# ble_lock_V1_2-20201223.net
KiCad netlist of a schematic drawn in Altium Designer
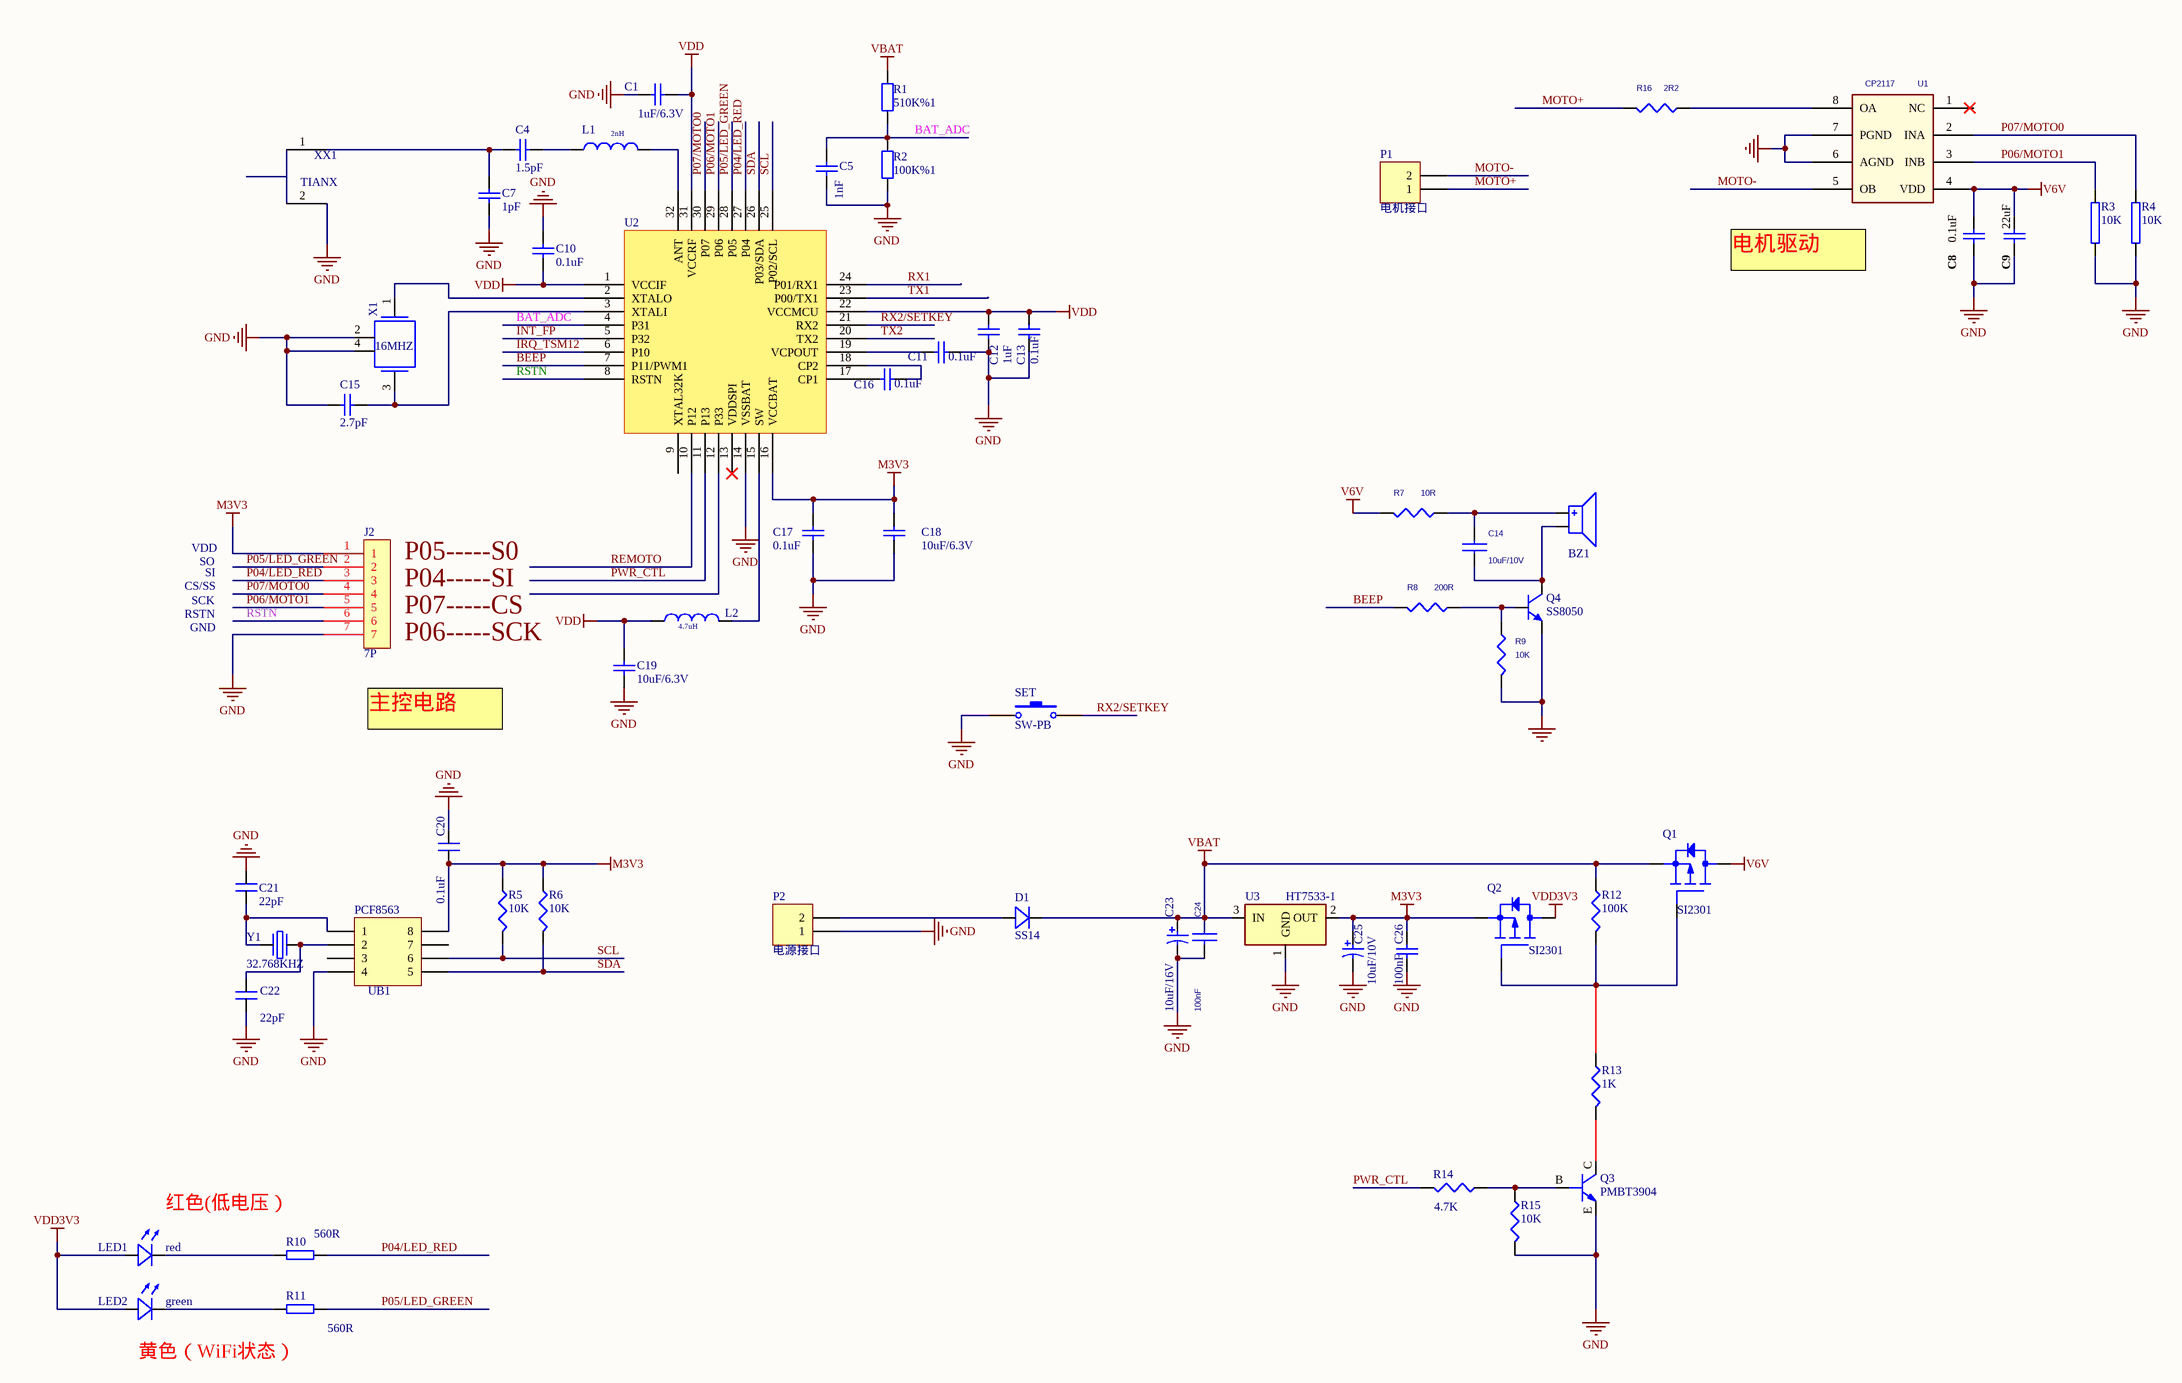
[diagram p0: ble_lock_V1.2-20201223.SchDoc]

(export (version "E")
  (design (tool "Eeschema 10.0.6"))
  (components
    (comp (ref "BZ1")
      (value "BUZZER")
      (footprint "BUZZER_D93_L40")
      (description "Buzzer")
      (libsource (lib "MyLibrary") (part "BUZZER"))
    )
    (comp (ref "C1")
      (value "1uF/6.3V")
      (footprint "0402C")
      (description "Capacitor")
      (fields (field (name "PUBLISHER") "Altium Limited"))
      (libsource (lib "MySchlib") (part "Cap"))
    )
    (comp (ref "C4")
      (value "1.5pF")
      (footprint "0603C")
      (description "Capacitor")
      (fields (field (name "PUBLISHER") "Altium Limited"))
      (libsource (lib "MySchlib") (part "Cap"))
    )
    (comp (ref "C5")
      (value "1nF")
      (footprint "0402C")
      (description "Capacitor, Ceramic")
      (fields (field (name "TOLERANCE") "5 %"))
      (libsource (lib "MyLibrary") (part "CAP-NP"))
    )
    (comp (ref "C7")
      (value "1pF")
      (footprint "0603C")
      (description "Capacitor")
      (fields (field (name "PUBLISHER") "Altium Limited"))
      (libsource (lib "MySchlib") (part "Cap"))
    )
    (comp (ref "C8")
      (value "0.1uF")
      (footprint "0402C")
      (description "Capacitor, Ceramic")
      (fields (field (name "TOLERANCE") "5 %"))
      (libsource (lib "MyLibrary") (part "CAP-NP"))
    )
    (comp (ref "C9")
      (value "22uF")
      (footprint "0805C")
      (description "Capacitor, Ceramic")
      (fields (field (name "TOLERANCE") "5 %"))
      (libsource (lib "MyLibrary") (part "CAP-NP"))
    )
    (comp (ref "C10")
      (value "0.1uF")
      (footprint "0402C")
      (description "Capacitor")
      (fields (field (name "PUBLISHER") "Altium Limited"))
      (libsource (lib "MySchlib") (part "Cap"))
    )
    (comp (ref "C11")
      (value "0.1uF")
      (footprint "0402C")
      (description "Capacitor")
      (fields (field (name "PUBLISHER") "Altium Limited"))
      (libsource (lib "MySchlib") (part "Cap"))
    )
    (comp (ref "C12")
      (value "1uF")
      (footprint "0402C")
      (description "Capacitor")
      (fields (field (name "PUBLISHER") "Altium Limited"))
      (libsource (lib "MySchlib") (part "Cap"))
    )
    (comp (ref "C13")
      (value "0.1uF")
      (footprint "0402C")
      (description "Capacitor")
      (fields (field (name "PUBLISHER") "Altium Limited"))
      (libsource (lib "MySchlib") (part "Cap"))
    )
    (comp (ref "C14") (value "10uF/10V") (footprint "0603C") (libsource (lib "*") (part "C_0_Dup1")))
    (comp (ref "C15")
      (value "2.7pF")
      (footprint "0402C")
      (description "Capacitor")
      (fields (field (name "PUBLISHER") "Altium Limited"))
      (libsource (lib "MySchlib") (part "Cap"))
    )
    (comp (ref "C16")
      (value "0.1uF")
      (footprint "0402C")
      (description "Capacitor")
      (fields (field (name "PUBLISHER") "Altium Limited"))
      (libsource (lib "MySchlib") (part "Cap"))
    )
    (comp (ref "C17")
      (value "0.1uF")
      (footprint "0402C")
      (description "Capacitor")
      (fields (field (name "PUBLISHER") "Altium Limited"))
      (libsource (lib "MySchlib") (part "Cap"))
    )
    (comp (ref "C18")
      (value "10uF/6.3V")
      (footprint "0603C")
      (description "Capacitor")
      (fields (field (name "PUBLISHER") "Altium Limited"))
      (libsource (lib "MySchlib") (part "Cap"))
    )
    (comp (ref "C19")
      (value "10uF/6.3V")
      (footprint "0603C")
      (description "Capacitor")
      (fields (field (name "PUBLISHER") "Altium Limited"))
      (libsource (lib "MySchlib") (part "Cap"))
    )
    (comp (ref "C20") (value "0.1uF") (footprint "0402C") (libsource (lib "自建元件库") (part "C")))
    (comp (ref "C21") (value "22pF") (footprint "0402C") (libsource (lib "自建元件库") (part "C")))
    (comp (ref "C22") (value "22pF") (footprint "0402C") (libsource (lib "自建元件库") (part "C")))
    (comp (ref "C23")
      (value "10uF/16V")
      (footprint "0805C")
      (description "Capacitor, tolerance ±20%")
      (libsource (lib "MySchLib") (part "CAP-P"))
    )
    (comp (ref "C24") (value "100nF") (footprint "0603C") (libsource (lib "*") (part "CAP NP")))
    (comp (ref "C25")
      (value "10uF/10V")
      (footprint "LC-0805_C")
      (description "Capacitor, tolerance ±20%")
      (libsource (lib "MySchLib") (part "CAP-P"))
    )
    (comp (ref "C26")
      (value "100nF")
      (footprint "0603C")
      (description "Capacitor, Ceramic")
      (fields (field (name "TOLERANCE") "5 %"))
      (libsource (lib "MyLibrary") (part "CAP-NP"))
    )
    (comp (ref "D1") (value "SS14") (footprint "DO-214AA") (libsource (lib "MySch") (part "D")))
    (comp (ref "J2") (value "7P") (footprint "7P-2.0MM") (libsource (lib "保险箱STM32") (part "7P")))
    (comp (ref "L1")
      (value "2nH")
      (footprint "0603L")
      (description "Power Inductor, 4.7uH, 0.7A, 260mR DCR")
      (fields
        (field (name "XMOS PART NUMBER") "E-09-0011")
        (field (name "MANUFACTURER") "Taiyo Yuden")
        (field (name "PART CREATOR") "JG")
        (field (name "APPROVED") "NO")
      )
      (libsource (lib "MySchlib") (part "INDUCTOR"))
    )
    (comp (ref "L2")
      (value "4.7uH")
      (footprint "0805L")
      (description "Power Inductor, 4.7uH, 0.7A, 260mR DCR")
      (fields
        (field (name "XMOS PART NUMBER") "E-09-0011")
        (field (name "MANUFACTURER") "Taiyo Yuden")
        (field (name "PART CREATOR") "JG")
        (field (name "APPROVED") "NO")
      )
      (libsource (lib "MySchlib") (part "INDUCTOR"))
    )
    (comp (ref "LED1") (value "red") (footprint "0603LED") (libsource (lib "MyLibrary") (part "LED")))
    (comp (ref "LED2") (value "green") (footprint "0603LED") (libsource (lib "MyLibrary") (part "LED")))
    (comp (ref "P1")
      (value "电机接口")
      (footprint "2P-1.25mm-弯脚")
      (description "Header, 2-Pin")
      (fields (field (name "PUBLISHER") "Altium Limited"))
      (libsource (lib "酒店锁模块") (part "Header 2"))
    )
    (comp (ref "P2")
      (value "电源接口")
      (footprint "2P-1.25mm-弯脚")
      (description "Header, 2-Pin")
      (fields (field (name "PUBLISHER") "Altium Limited"))
      (libsource (lib "酒店锁模块") (part "Header 2"))
    )
    (comp (ref "Q1")
      (value "SI2301")
      (footprint "SOT-23 - GDS")
      (libsource (lib "*") (part "PWRMOSFET_EP_DGS_0"))
    )
    (comp (ref "Q2")
      (value "SI2301")
      (footprint "SOT-23 - GDS")
      (libsource (lib "*") (part "PWRMOSFET_EP_DGS_0"))
    )
    (comp (ref "Q3") (value "PMBT3904") (footprint "SOT-23 - BCE") (libsource (lib "*") (part "PMBT3904")))
    (comp (ref "Q4")
      (value "SS8050")
      (footprint "SOT-23-3L")
      (description "Bipolar Junction Transistor")
      (libsource (lib "MyLibrary") (part "NPN_BJT"))
    )
    (comp (ref "R1")
      (value "510K%1")
      (footprint "0402R")
      (description "Resistor")
      (libsource (lib "MyLibrary") (part "Res2"))
    )
    (comp (ref "R2")
      (value "100K%1")
      (footprint "0402R")
      (description "Resistor")
      (libsource (lib "MyLibrary") (part "Res2"))
    )
    (comp (ref "R3") (value "10K") (footprint "0402R") (libsource (lib "*") (part "Pro71C3.TMP_UnNamed_1")))
    (comp (ref "R4") (value "10K") (footprint "0402R") (libsource (lib "*") (part "Pro71C3.TMP_UnNamed_1")))
    (comp (ref "R5") (value "10K") (footprint "0402R") (libsource (lib "*") (part "R")))
    (comp (ref "R6") (value "10K") (footprint "0402R") (libsource (lib "*") (part "R")))
    (comp (ref "R7") (value "10R") (footprint "0402R") (libsource (lib "*") (part "R_Dup1")))
    (comp (ref "R8") (value "200R") (footprint "0402R") (libsource (lib "*") (part "R_Dup1")))
    (comp (ref "R9") (value "10K") (footprint "0402R") (libsource (lib "*") (part "R_Dup1")))
    (comp (ref "R10") (value "560R") (footprint "0402R") (libsource (lib "MySch") (part "R")))
    (comp (ref "R11") (value "560R") (footprint "0402R") (libsource (lib "MySch") (part "R")))
    (comp (ref "R12") (value "100K") (footprint "0402R") (libsource (lib "*") (part "R")))
    (comp (ref "R13") (value "1K") (footprint "0402R") (libsource (lib "*") (part "R")))
    (comp (ref "R14") (value "4.7K") (footprint "0402R") (libsource (lib "*") (part "R")))
    (comp (ref "R15") (value "10K") (footprint "0402R") (libsource (lib "*") (part "R")))
    (comp (ref "R16") (value "2R2") (footprint "0603R") (libsource (lib "*") (part "R_Dup1")))
    (comp (ref "SET")
      (value "SW-PB")
      (footprint "SET")
      (description "Switch")
      (fields (field (name "PUBLISHER") "Altium Limited"))
      (libsource (lib "Miscellaneous Devices") (part "SW-PB"))
    )
    (comp (ref "U1") (value "CP2117") (footprint "SOP8") (libsource (lib "*") (part "AM24LC02_0")))
    (comp (ref "U2")
      (value "BK3431Q")
      (footprint "QFN32_4*4*0.4")
      (libsource (lib "BK3431") (part "BK3431Q"))
    )
    (comp (ref "U3") (value "HT7533-1") (footprint "SOT-23-3L") (libsource (lib "*") (part "XC6206P302M")))
    (comp (ref "UB1") (value "PCF8563") (footprint "SOP8") (libsource (lib "MySch") (part "IC8")))
    (comp (ref "X1")
      (value "16MHZ")
      (footprint "XTAL3225")
      (fields
        (field (name "XMOS PART NUMBER") "E-07-0030")
        (field (name "MANUFACTURER") "Abracon")
        (field (name "MANUFACTURER PART NUMBER") "ABLS-24.000MHz-B4")
        (field (name "PART CREATOR") "JG")
        (field (name "APPROVED") "NO")
      )
      (libsource (lib "MySchlib") (part "OSC"))
    )
    (comp (ref "XX1")
      (value "TIANX")
      (footprint "BT_NAMI_NO")
      (libsource (lib "885阿里云PCB_Project1") (part "TIANX"))
    )
    (comp (ref "Y1") (value "32.768KHZ") (footprint "晶振") (libsource (lib "MySch") (part "晶振")))
  )
  (nets
    (net (code "1") (name "/BAT_ADC") (class "Default")
      (node (ref "C5") (pin "2") (pinfunction "2_2") (pintype "passive"))
      (node (ref "R1") (pin "2") (pinfunction "2_2") (pintype "passive"))
      (node (ref "R2") (pin "1") (pinfunction "1_1") (pintype "passive"))
      (node (ref "U2") (pin "4") (pinfunction "P31_4") (pintype "passive"))
    )
    (net (code "2") (name "/BEEP") (class "Default")
      (node (ref "R8") (pin "2") (pinfunction "2_2") (pintype "passive"))
      (node (ref "U2") (pin "7") (pinfunction "P11/PWM1_7") (pintype "passive"))
    )
    (net (code "3") (name "/INT_FP") (class "Default")
      (node (ref "U2") (pin "5") (pinfunction "P32_5") (pintype "passive"))
    )
    (net (code "4") (name "/IRQ_TSM12") (class "Default")
      (node (ref "U2") (pin "6") (pinfunction "P10_6") (pintype "passive"))
    )
    (net (code "5") (name "/MOTO+") (class "Default")
      (node (ref "P1") (pin "1") (pinfunction "1_1") (pintype "passive"))
      (node (ref "R16") (pin "2") (pinfunction "2_2") (pintype "passive"))
    )
    (net (code "6") (name "/MOTO-") (class "Default")
      (node (ref "P1") (pin "2") (pinfunction "2_2") (pintype "passive"))
      (node (ref "U1") (pin "5") (pinfunction "OB_5") (pintype "passive"))
    )
    (net (code "7") (name "/P04{slash}LED_RED") (class "Default")
      (node (ref "J2") (pin "3") (pinfunction "3_3") (pintype "passive"))
      (node (ref "R10") (pin "2") (pintype "passive"))
      (node (ref "U2") (pin "27") (pinfunction "P04_27") (pintype "passive"))
    )
    (net (code "8") (name "/P05{slash}LED_GREEN") (class "Default")
      (node (ref "J2") (pin "2") (pinfunction "2_2") (pintype "passive"))
      (node (ref "R11") (pin "2") (pintype "passive"))
      (node (ref "U2") (pin "28") (pinfunction "P05_28") (pintype "passive"))
    )
    (net (code "9") (name "/P06{slash}MOTO1") (class "Default")
      (node (ref "J2") (pin "5") (pinfunction "5_5") (pintype "passive"))
      (node (ref "R3") (pin "2") (pintype "passive"))
      (node (ref "U1") (pin "3") (pinfunction "INB_3") (pintype "passive"))
      (node (ref "U2") (pin "29") (pinfunction "P06_29") (pintype "passive"))
    )
    (net (code "10") (name "/P07{slash}MOTO0") (class "Default")
      (node (ref "J2") (pin "4") (pinfunction "4_4") (pintype "passive"))
      (node (ref "R4") (pin "2") (pintype "passive"))
      (node (ref "U1") (pin "2") (pinfunction "INA_2") (pintype "passive"))
      (node (ref "U2") (pin "30") (pinfunction "P07_30") (pintype "passive"))
    )
    (net (code "11") (name "/PWR_CTL") (class "Default")
      (node (ref "R14") (pin "2") (pinfunction "2_2") (pintype "passive"))
      (node (ref "U2") (pin "11") (pinfunction "P13_11") (pintype "passive"))
    )
    (net (code "12") (name "/REMOTO") (class "Default")
      (node (ref "U2") (pin "10") (pinfunction "P12_10") (pintype "passive"))
    )
    (net (code "13") (name "/RSTN") (class "Default")
      (node (ref "J2") (pin "6") (pinfunction "6_6") (pintype "passive"))
      (node (ref "U2") (pin "8") (pinfunction "RSTN_8") (pintype "passive"))
    )
    (net (code "14") (name "/RX1") (class "Default")
      (node (ref "U2") (pin "24") (pinfunction "P01/RX1_24") (pintype "passive"))
    )
    (net (code "15") (name "/RX2{slash}SETKEY") (class "Default")
      (node (ref "SET") (pin "1") (pinfunction "1_1") (pintype "passive"))
      (node (ref "U2") (pin "21") (pinfunction "RX2_21") (pintype "passive"))
    )
    (net (code "16") (name "/SCL") (class "Default")
      (node (ref "R5") (pin "2") (pinfunction "2_2") (pintype "passive"))
      (node (ref "U2") (pin "25") (pinfunction "P02/SCL_25") (pintype "passive"))
      (node (ref "UB1") (pin "6") (pinfunction "6_6") (pintype "passive"))
    )
    (net (code "17") (name "/SDA") (class "Default")
      (node (ref "R6") (pin "2") (pinfunction "2_2") (pintype "passive"))
      (node (ref "U2") (pin "26") (pinfunction "P03/SDA_26") (pintype "passive"))
      (node (ref "UB1") (pin "5") (pinfunction "5_5") (pintype "passive"))
    )
    (net (code "18") (name "/TX1") (class "Default")
      (node (ref "U2") (pin "23") (pinfunction "P00/TX1_23") (pintype "passive"))
    )
    (net (code "19") (name "/TX2") (class "Default")
      (node (ref "U2") (pin "20") (pinfunction "TX2_20") (pintype "passive"))
    )
    (net (code "20") (name "GND") (class "Default")
      (node (ref "C1") (pin "1") (pinfunction "1_1") (pintype "passive"))
      (node (ref "C10") (pin "1") (pinfunction "1_1") (pintype "passive"))
      (node (ref "C11") (pin "2") (pinfunction "2_2") (pintype "passive"))
      (node (ref "C12") (pin "1") (pinfunction "1_1") (pintype "passive"))
      (node (ref "C13") (pin "1") (pinfunction "1_1") (pintype "passive"))
      (node (ref "C15") (pin "1") (pinfunction "1_1") (pintype "passive"))
      (node (ref "C17") (pin "2") (pinfunction "2_2") (pintype "passive"))
      (node (ref "C18") (pin "2") (pinfunction "2_2") (pintype "passive"))
      (node (ref "C19") (pin "1") (pinfunction "1_1") (pintype "passive"))
      (node (ref "C20") (pin "2") (pintype "passive"))
      (node (ref "C21") (pin "2") (pintype "passive"))
      (node (ref "C22") (pin "1") (pintype "passive"))
      (node (ref "C23") (pin "2") (pinfunction "2_2") (pintype "passive"))
      (node (ref "C24") (pin "2") (pinfunction "2_2") (pintype "passive"))
      (node (ref "C25") (pin "2") (pinfunction "2_2") (pintype "passive"))
      (node (ref "C26") (pin "2") (pinfunction "2_2") (pintype "passive"))
      (node (ref "C5") (pin "1") (pinfunction "1_1") (pintype "passive"))
      (node (ref "C7") (pin "1") (pinfunction "1_1") (pintype "passive"))
      (node (ref "C8") (pin "2") (pinfunction "2_2") (pintype "passive"))
      (node (ref "C9") (pin "2") (pinfunction "2_2") (pintype "passive"))
      (node (ref "J2") (pin "7") (pinfunction "7_7") (pintype "passive"))
      (node (ref "P2") (pin "1") (pinfunction "1_1") (pintype "passive"))
      (node (ref "Q3") (pin "E") (pinfunction "EMITTER_E") (pintype "passive"))
      (node (ref "Q4") (pin "2") (pinfunction "2_2") (pintype "passive"))
      (node (ref "R15") (pin "2") (pinfunction "2_2") (pintype "passive"))
      (node (ref "R2") (pin "2") (pinfunction "2_2") (pintype "passive"))
      (node (ref "R3") (pin "1") (pintype "passive"))
      (node (ref "R4") (pin "1") (pintype "passive"))
      (node (ref "R9") (pin "2") (pinfunction "2_2") (pintype "passive"))
      (node (ref "SET") (pin "2") (pinfunction "2_2") (pintype "passive"))
      (node (ref "U1") (pin "6") (pinfunction "AGND_6") (pintype "passive"))
      (node (ref "U1") (pin "7") (pinfunction "PGND_7") (pintype "passive"))
      (node (ref "U2") (pin "14") (pinfunction "VSSBAT_14") (pintype "passive"))
      (node (ref "U3") (pin "1") (pinfunction "GND_1") (pintype "passive"))
      (node (ref "UB1") (pin "4") (pinfunction "4_4") (pintype "passive"))
      (node (ref "X1") (pin "2") (pintype "passive"))
      (node (ref "X1") (pin "4") (pintype "passive"))
      (node (ref "XX1") (pin "2") (pinfunction "2_2") (pintype "passive"))
    )
    (net (code "21") (name "M3V3") (class "Default")
      (node (ref "C17") (pin "1") (pinfunction "1_1") (pintype "passive"))
      (node (ref "C18") (pin "1") (pinfunction "1_1") (pintype "passive"))
      (node (ref "C20") (pin "1") (pintype "passive"))
      (node (ref "C25") (pin "1") (pinfunction "1_1") (pintype "passive"))
      (node (ref "C26") (pin "1") (pinfunction "1_1") (pintype "passive"))
      (node (ref "J2") (pin "1") (pinfunction "1_1") (pintype "passive"))
      (node (ref "Q2") (pin "S") (pinfunction "SOURCE_S") (pintype "passive"))
      (node (ref "R5") (pin "1") (pinfunction "1_1") (pintype "passive"))
      (node (ref "R6") (pin "1") (pinfunction "1_1") (pintype "passive"))
      (node (ref "U2") (pin "16") (pinfunction "VCCBAT_16") (pintype "passive"))
      (node (ref "U3") (pin "2") (pinfunction "OUT_2") (pintype "passive"))
      (node (ref "UB1") (pin "8") (pinfunction "8_8") (pintype "passive"))
    )
    (net (code "22") (name "Net-(BZ1-Pad1)") (class "Default")
      (node (ref "BZ1") (pin "1") (pintype "passive"))
      (node (ref "C14") (pin "2") (pinfunction "2_2") (pintype "passive"))
      (node (ref "R7") (pin "1") (pinfunction "1_1") (pintype "passive"))
    )
    (net (code "23") (name "Net-(BZ1-Pad2)") (class "Default")
      (node (ref "BZ1") (pin "2") (pintype "passive"))
      (node (ref "C14") (pin "1") (pinfunction "1_1") (pintype "passive"))
      (node (ref "Q4") (pin "3") (pinfunction "3_3") (pintype "passive"))
    )
    (net (code "24") (name "Net-(C4-Pad2)") (class "Default")
      (node (ref "C4") (pin "2") (pinfunction "2_2") (pintype "passive"))
      (node (ref "C7") (pin "2") (pinfunction "2_2") (pintype "passive"))
      (node (ref "XX1") (pin "1") (pinfunction "1_1") (pintype "passive"))
    )
    (net (code "25") (name "Net-(C21-Pad1)") (class "Default")
      (node (ref "C21") (pin "1") (pintype "passive"))
      (node (ref "UB1") (pin "1") (pinfunction "1_1") (pintype "passive"))
      (node (ref "Y1") (pin "2") (pintype "passive"))
    )
    (net (code "26") (name "Net-(C22-Pad2)") (class "Default")
      (node (ref "C22") (pin "2") (pintype "passive"))
      (node (ref "UB1") (pin "2") (pinfunction "2_2") (pintype "passive"))
      (node (ref "Y1") (pin "1") (pintype "passive"))
    )
    (net (code "27") (name "Net-(D1-A)") (class "Default")
      (node (ref "D1") (pin "1") (pinfunction "A_1") (pintype "passive"))
      (node (ref "P2") (pin "2") (pinfunction "2_2") (pintype "passive"))
    )
    (net (code "28") (name "Net-(L1-P1)") (class "Default")
      (node (ref "C4") (pin "1") (pinfunction "1_1") (pintype "passive"))
      (node (ref "L1") (pin "1") (pinfunction "P1_1") (pintype "passive"))
    )
    (net (code "29") (name "Net-(L1-P2)") (class "Default")
      (node (ref "L1") (pin "2") (pinfunction "P2_2") (pintype "passive"))
      (node (ref "U2") (pin "32") (pinfunction "ANT_32") (pintype "passive"))
    )
    (net (code "30") (name "Net-(L2-P2)") (class "Default")
      (node (ref "L2") (pin "2") (pinfunction "P2_2") (pintype "passive"))
      (node (ref "U2") (pin "15") (pinfunction "SW_15") (pintype "passive"))
    )
    (net (code "31") (name "Net-(LED1-Pad2)") (class "Default")
      (node (ref "LED1") (pin "2") (pintype "passive"))
      (node (ref "R10") (pin "1") (pintype "passive"))
    )
    (net (code "32") (name "Net-(LED2-Pad2)") (class "Default")
      (node (ref "LED2") (pin "2") (pintype "passive"))
      (node (ref "R11") (pin "1") (pintype "passive"))
    )
    (net (code "33") (name "Net-(Q1-GATE)") (class "Default")
      (node (ref "Q1") (pin "G") (pinfunction "GATE_G") (pintype "passive"))
      (node (ref "Q2") (pin "G") (pinfunction "GATE_G") (pintype "passive"))
      (node (ref "R12") (pin "2") (pinfunction "2_2") (pintype "passive"))
      (node (ref "R13") (pin "1") (pinfunction "1_1") (pintype "passive"))
    )
    (net (code "34") (name "Net-(Q3-BASE)") (class "Default")
      (node (ref "Q3") (pin "B") (pinfunction "BASE_B") (pintype "passive"))
      (node (ref "R14") (pin "1") (pinfunction "1_1") (pintype "passive"))
      (node (ref "R15") (pin "1") (pinfunction "1_1") (pintype "passive"))
    )
    (net (code "35") (name "Net-(Q3-COLLECTOR)") (class "Default")
      (node (ref "Q3") (pin "C") (pinfunction "COLLECTOR_C") (pintype "passive"))
      (node (ref "R13") (pin "2") (pinfunction "2_2") (pintype "passive"))
    )
    (net (code "36") (name "Net-(Q4-Pad1)") (class "Default")
      (node (ref "Q4") (pin "1") (pinfunction "1_1") (pintype "passive"))
      (node (ref "R8") (pin "1") (pinfunction "1_1") (pintype "passive"))
      (node (ref "R9") (pin "1") (pinfunction "1_1") (pintype "passive"))
    )
    (net (code "37") (name "Net-(U1-OA)") (class "Default")
      (node (ref "R16") (pin "1") (pinfunction "1_1") (pintype "passive"))
      (node (ref "U1") (pin "8") (pinfunction "OA_8") (pintype "passive"))
    )
    (net (code "38") (name "Net-(U2-CP1)") (class "Default")
      (node (ref "C16") (pin "1") (pinfunction "1_1") (pintype "passive"))
      (node (ref "U2") (pin "17") (pinfunction "CP1_17") (pintype "passive"))
    )
    (net (code "39") (name "Net-(U2-CP2)") (class "Default")
      (node (ref "C16") (pin "2") (pinfunction "2_2") (pintype "passive"))
      (node (ref "U2") (pin "18") (pinfunction "CP2_18") (pintype "passive"))
    )
    (net (code "40") (name "Net-(U2-VCPOUT)") (class "Default")
      (node (ref "C11") (pin "1") (pinfunction "1_1") (pintype "passive"))
      (node (ref "U2") (pin "19") (pinfunction "VCPOUT_19") (pintype "passive"))
    )
    (net (code "41") (name "Net-(U2-XTALI)") (class "Default")
      (node (ref "C15") (pin "2") (pinfunction "2_2") (pintype "passive"))
      (node (ref "U2") (pin "3") (pinfunction "XTALI_3") (pintype "passive"))
      (node (ref "X1") (pin "3") (pintype "passive"))
    )
    (net (code "42") (name "Net-(U2-XTALO)") (class "Default")
      (node (ref "U2") (pin "2") (pinfunction "XTALO_2") (pintype "passive"))
      (node (ref "X1") (pin "1") (pintype "passive"))
    )
    (net (code "43") (name "V6V") (class "Default")
      (node (ref "C8") (pin "1") (pinfunction "1_1") (pintype "passive"))
      (node (ref "C9") (pin "1") (pinfunction "1_1") (pintype "passive"))
      (node (ref "Q1") (pin "D") (pinfunction "DRAIN_D") (pintype "passive"))
      (node (ref "R7") (pin "2") (pinfunction "2_2") (pintype "passive"))
      (node (ref "U1") (pin "4") (pinfunction "VDD_4") (pintype "passive"))
    )
    (net (code "44") (name "VBAT") (class "Default")
      (node (ref "C23") (pin "1") (pinfunction "1_1") (pintype "passive"))
      (node (ref "C24") (pin "1") (pinfunction "1_1") (pintype "passive"))
      (node (ref "D1") (pin "2") (pinfunction "K_2") (pintype "passive"))
      (node (ref "Q1") (pin "S") (pinfunction "SOURCE_S") (pintype "passive"))
      (node (ref "R1") (pin "1") (pinfunction "1_1") (pintype "passive"))
      (node (ref "R12") (pin "1") (pinfunction "1_1") (pintype "passive"))
      (node (ref "U3") (pin "3") (pinfunction "IN_3") (pintype "passive"))
    )
    (net (code "45") (name "VDD") (class "Default")
      (node (ref "C1") (pin "2") (pinfunction "2_2") (pintype "passive"))
      (node (ref "C10") (pin "2") (pinfunction "2_2") (pintype "passive"))
      (node (ref "C12") (pin "2") (pinfunction "2_2") (pintype "passive"))
      (node (ref "C13") (pin "2") (pinfunction "2_2") (pintype "passive"))
      (node (ref "C19") (pin "2") (pinfunction "2_2") (pintype "passive"))
      (node (ref "L2") (pin "1") (pinfunction "P1_1") (pintype "passive"))
      (node (ref "U2") (pin "1") (pinfunction "VCCIF_1") (pintype "passive"))
      (node (ref "U2") (pin "22") (pinfunction "VCCMCU_22") (pintype "passive"))
      (node (ref "U2") (pin "31") (pinfunction "VCCRF_31") (pintype "passive"))
    )
    (net (code "46") (name "VDD3V3") (class "Default")
      (node (ref "LED1") (pin "1") (pintype "passive"))
      (node (ref "LED2") (pin "1") (pintype "passive"))
      (node (ref "Q2") (pin "D") (pinfunction "DRAIN_D") (pintype "passive"))
    )
    (net (code "47") (name "unconnected-(U1-NC-Pad1)") (class "Default")
      (node (ref "U1") (pin "1") (pinfunction "NC_1") (pintype "passive"))
    )
    (net (code "48") (name "unconnected-(U2-P33-Pad12)") (class "Default")
      (node (ref "U2") (pin "12") (pinfunction "P33_12") (pintype "passive"))
    )
    (net (code "49") (name "unconnected-(U2-VDDSPI-Pad13)") (class "Default")
      (node (ref "U2") (pin "13") (pinfunction "VDDSPI_13") (pintype "passive+no_connect"))
    )
    (net (code "50") (name "unconnected-(U2-XTAL32K-Pad9)") (class "Default")
      (node (ref "U2") (pin "9") (pinfunction "XTAL32K_9") (pintype "passive"))
    )
    (net (code "51") (name "unconnected-(UB1-Pad3)") (class "Default")
      (node (ref "UB1") (pin "3") (pinfunction "3_3") (pintype "passive"))
    )
    (net (code "52") (name "unconnected-(UB1-Pad7)") (class "Default")
      (node (ref "UB1") (pin "7") (pinfunction "7_7") (pintype "passive"))
    )
  )
)
